# SCH_Tiny_printer_small_2024-12-16.net
KiCad netlist of a schematic drawn in EasyEDA
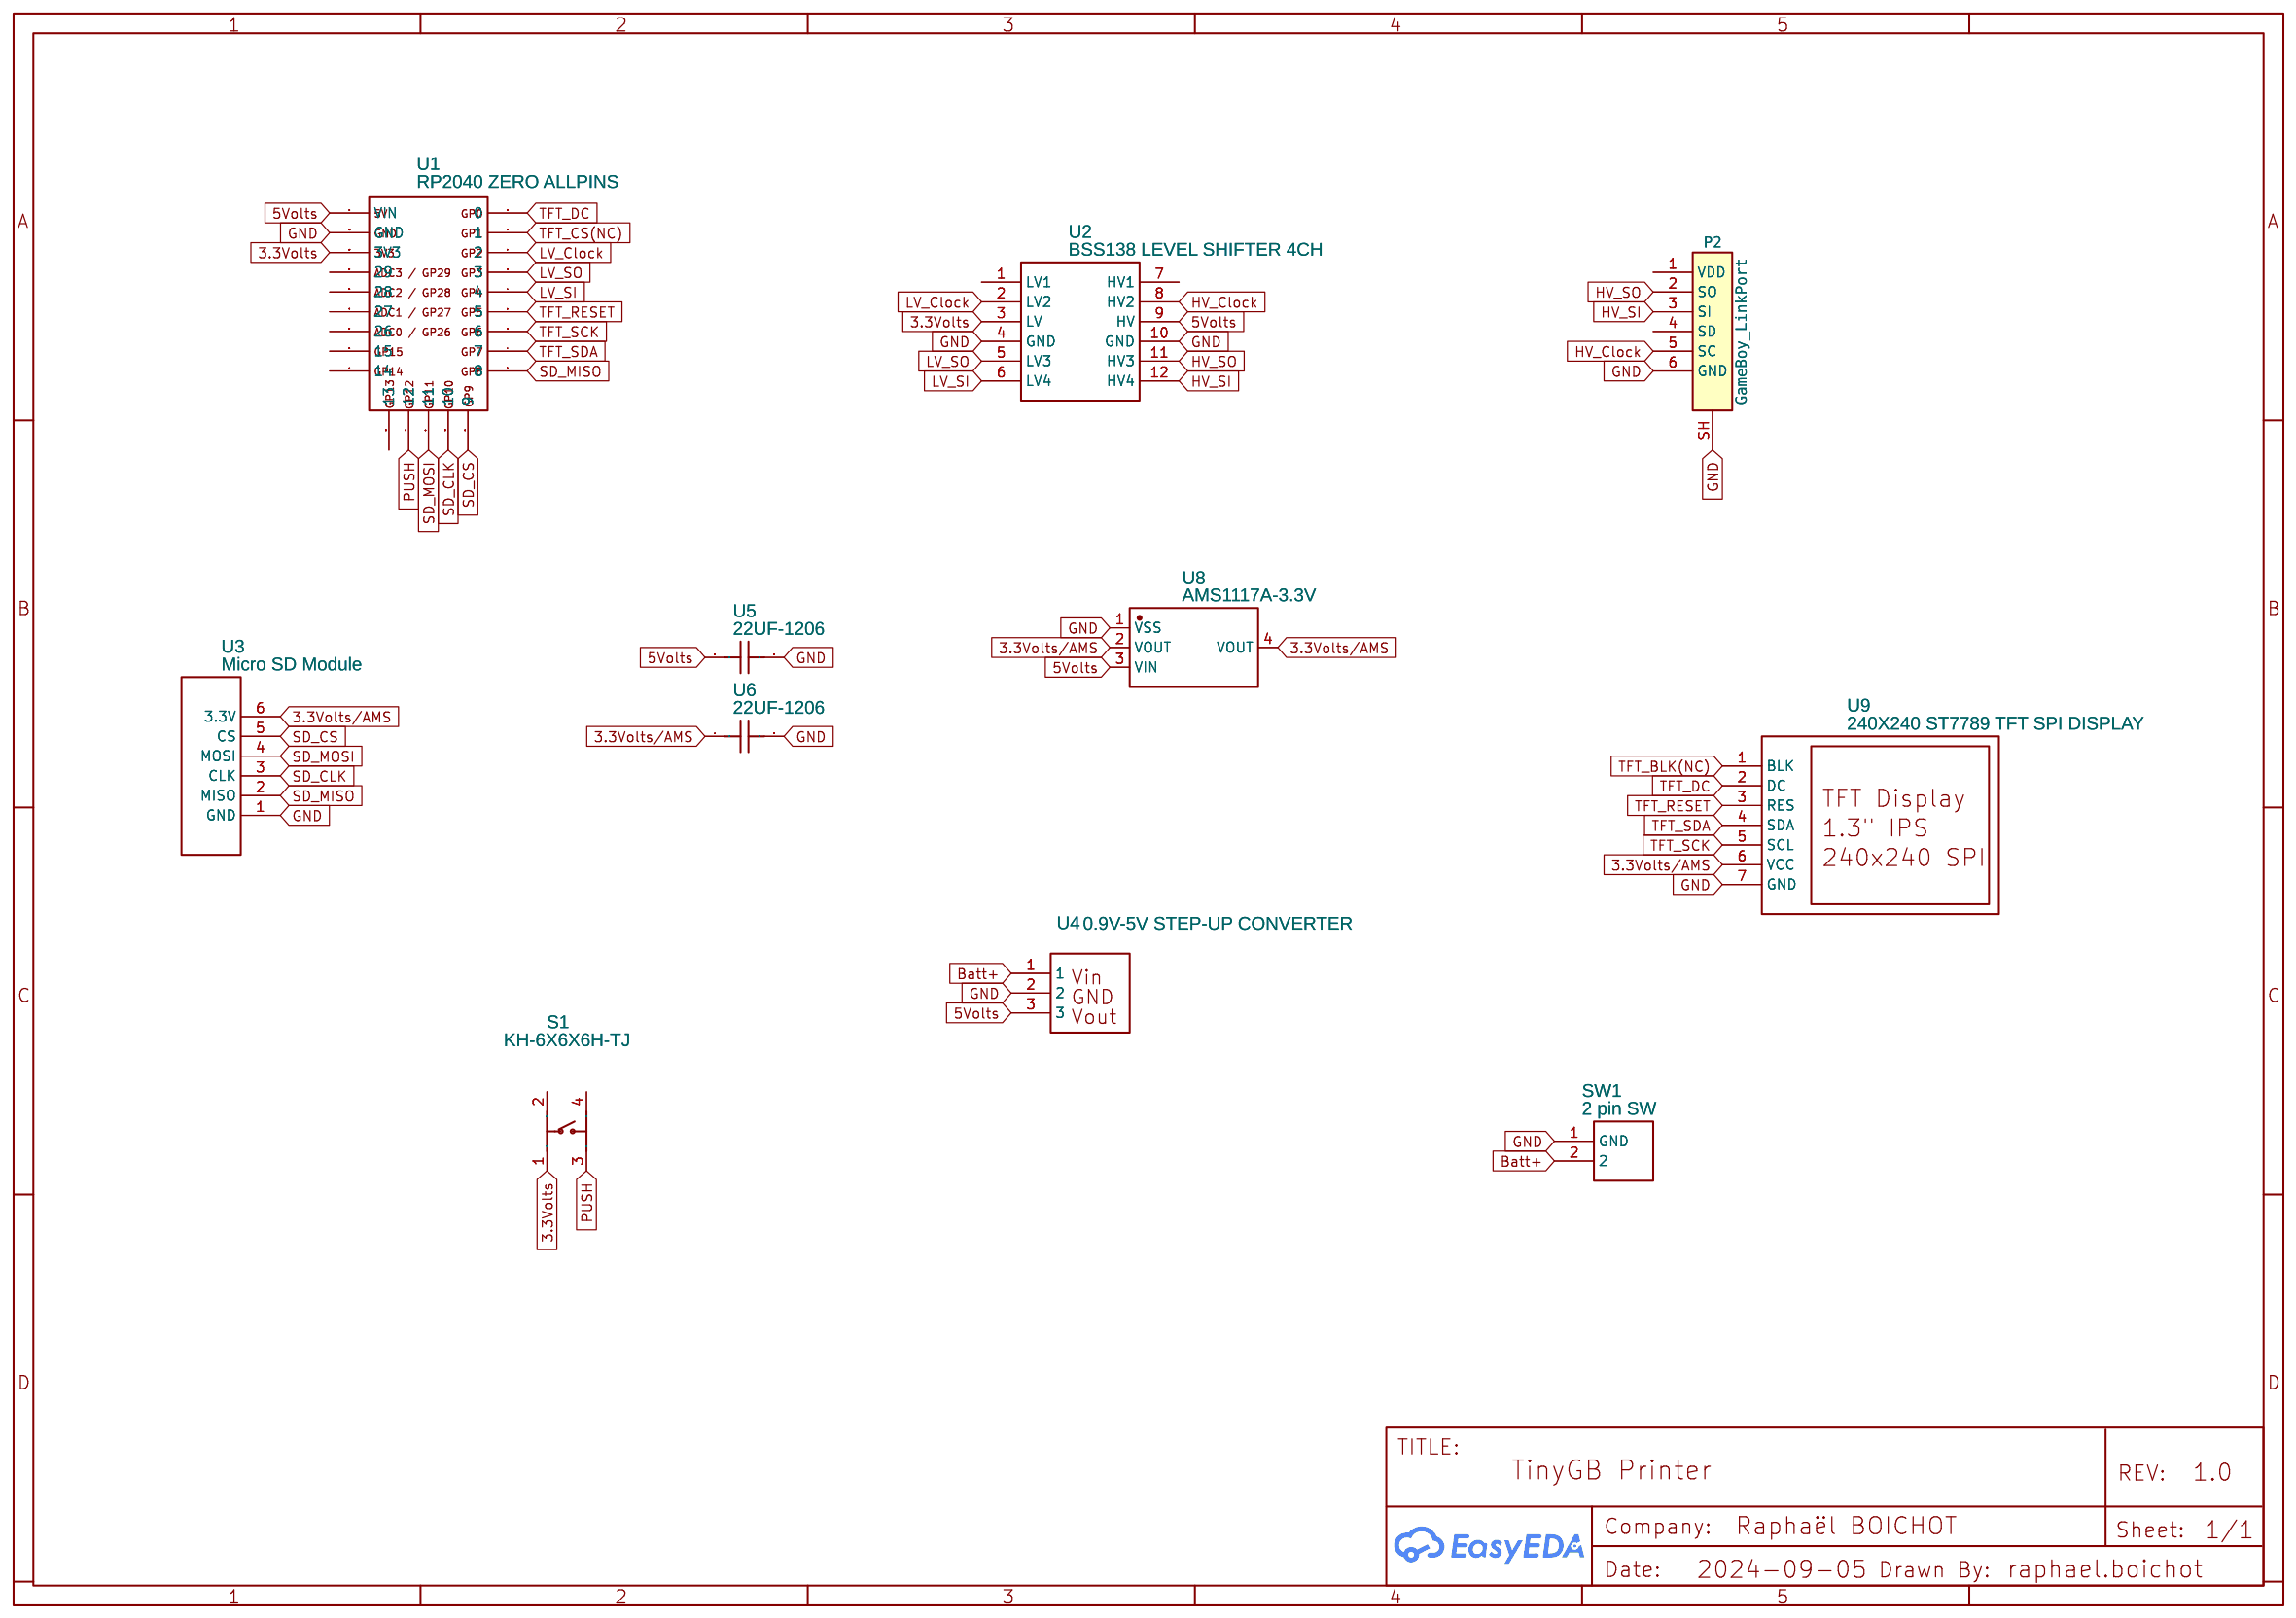
[diagram p0: schematic sheet]

(export (version "E")
  (design (tool "Eeschema 10.0.6"))
  (components
    (comp (ref "P2") (value "GameBoy_LinkPort") (libsource (lib "") (part "Unknown_860_-645")))
    (comp (ref "S1")
      (value "KH-6X6X6H-TJ")
      (fields (field (name "Manufacturer") "kinghelm(金航标)"))
      (libsource (lib "") (part "KH-6X6X6H-TJ"))
    )
    (comp (ref "SW1")
      (value "2 pin SW")
      (fields (field (name "Manufacturer") "NA"))
      (libsource (lib "") (part "2 pin SW"))
    )
    (comp (ref "U1")
      (value "RP2040 ZERO ALLPINS")
      (fields (field (name "Manufacturer Part") "RP2040 Zero") (field (name "Manufacturer") "Waveshare"))
      (libsource (lib "") (part "RP2040 ZERO ALLPINS"))
    )
    (comp (ref "U2")
      (value "BSS138 LEVEL SHIFTER 4CH")
      (fields (field (name "Manufacturer Part") "BSS138") (field (name "Manufacturer") "ON Semiconductor"))
      (libsource (lib "") (part "BSS138 LEVEL SHIFTER 4CH"))
    )
    (comp (ref "U3") (value "Micro SD Module") (libsource (lib "") (part "Micro SD Module")))
    (comp (ref "U4")
      (value "0.9V-5V STEP-UP CONVERTER")
      (fields (field (name "Manufacturer") "Generic"))
      (libsource (lib "") (part "0.9V-5V STEP-UP CONVERTER"))
    )
    (comp (ref "U5")
      (value "22UF-1206")
      (fields (field (name "Manufacturer Part") "220UF-1206"))
      (libsource (lib "") (part "220UF-1206"))
    )
    (comp (ref "U6")
      (value "22UF-1206")
      (fields (field (name "Manufacturer Part") "220UF-1206"))
      (libsource (lib "") (part "220UF-1206"))
    )
    (comp (ref "U8")
      (value "AMS1117A-3.3V")
      (fields (field (name "Manufacturer") "HX(恒佳兴)"))
      (libsource (lib "") (part "AMS1117A-3.3V"))
    )
    (comp (ref "U9")
      (value "240X240 ST7789 TFT SPI DISPLAY")
      (libsource (lib "") (part "240X240 ST7789 TFT SPI DISPLAY"))
    )
  )
  (nets
    (net (code "1") (name "3.3Volts") (class "Default")
      (node (ref "S1") (pin "1") (pinfunction "1_1") (pintype "unspecified"))
      (node (ref "U1") (pin "3V3") (pinfunction "3V3_3V3") (pintype "unspecified"))
      (node (ref "U2") (pin "3") (pinfunction "LV_3") (pintype "passive"))
    )
    (net (code "2") (name "3.3Volts{slash}AMS") (class "Default")
      (node (ref "U3") (pin "6") (pinfunction "3.3V_6") (pintype "unspecified"))
      (node (ref "U6") (pin "1") (pinfunction "1_1") (pintype "unspecified"))
      (node (ref "U8") (pin "2") (pinfunction "VOUT_2") (pintype "unspecified"))
      (node (ref "U8") (pin "4") (pinfunction "VOUT_4") (pintype "unspecified"))
      (node (ref "U9") (pin "6") (pinfunction "VCC_6") (pintype "unspecified"))
    )
    (net (code "3") (name "5Volts") (class "Default")
      (node (ref "U1") (pin "VIN") (pinfunction "VIN_VIN") (pintype "unspecified"))
      (node (ref "U2") (pin "9") (pinfunction "HV_9") (pintype "passive"))
      (node (ref "U4") (pin "3") (pinfunction "3_3") (pintype "unspecified"))
      (node (ref "U5") (pin "1") (pinfunction "1_1") (pintype "unspecified"))
      (node (ref "U8") (pin "3") (pinfunction "VIN_3") (pintype "unspecified"))
    )
    (net (code "4") (name "Batt+") (class "Default")
      (node (ref "SW1") (pin "2") (pinfunction "2_2") (pintype "unspecified"))
      (node (ref "U4") (pin "1") (pinfunction "1_1") (pintype "unspecified"))
    )
    (net (code "5") (name "GND") (class "Default")
      (node (ref "P2") (pin "6") (pinfunction "GND_6") (pintype "unspecified"))
      (node (ref "P2") (pin "SH") (pintype "unspecified"))
      (node (ref "SW1") (pin "1") (pinfunction "GND_1") (pintype "unspecified"))
      (node (ref "U1") (pin "GND") (pinfunction "GND_GND") (pintype "unspecified"))
      (node (ref "U2") (pin "10") (pinfunction "GND_10") (pintype "passive"))
      (node (ref "U2") (pin "4") (pinfunction "GND_4") (pintype "passive"))
      (node (ref "U3") (pin "1") (pinfunction "GND_1") (pintype "unspecified"))
      (node (ref "U4") (pin "2") (pinfunction "2_2") (pintype "unspecified"))
      (node (ref "U5") (pin "2") (pinfunction "2_2") (pintype "unspecified"))
      (node (ref "U6") (pin "2") (pinfunction "2_2") (pintype "unspecified"))
      (node (ref "U8") (pin "1") (pinfunction "VSS_1") (pintype "unspecified"))
      (node (ref "U9") (pin "7") (pinfunction "GND_7") (pintype "unspecified"))
    )
    (net (code "6") (name "HV_Clock") (class "Default")
      (node (ref "P2") (pin "5") (pinfunction "SC_5") (pintype "unspecified"))
      (node (ref "U2") (pin "8") (pinfunction "HV2_8") (pintype "output"))
    )
    (net (code "7") (name "HV_SI") (class "Default")
      (node (ref "P2") (pin "3") (pinfunction "SI_3") (pintype "unspecified"))
      (node (ref "U2") (pin "12") (pinfunction "HV4_12") (pintype "output"))
    )
    (net (code "8") (name "HV_SO") (class "Default")
      (node (ref "P2") (pin "2") (pinfunction "SO_2") (pintype "unspecified"))
      (node (ref "U2") (pin "11") (pinfunction "HV3_11") (pintype "output"))
    )
    (net (code "9") (name "LV_Clock") (class "Default")
      (node (ref "U1") (pin "2") (pinfunction "2_2") (pintype "unspecified"))
      (node (ref "U2") (pin "2") (pinfunction "LV2_2") (pintype "input"))
    )
    (net (code "10") (name "LV_SI") (class "Default")
      (node (ref "U1") (pin "4") (pinfunction "4_4") (pintype "unspecified"))
      (node (ref "U2") (pin "6") (pinfunction "LV4_6") (pintype "input"))
    )
    (net (code "11") (name "LV_SO") (class "Default")
      (node (ref "U1") (pin "3") (pinfunction "3_3") (pintype "unspecified"))
      (node (ref "U2") (pin "5") (pinfunction "LV3_5") (pintype "input"))
    )
    (net (code "12") (name "PUSH") (class "Default")
      (node (ref "S1") (pin "3") (pinfunction "3_3") (pintype "unspecified"))
      (node (ref "U1") (pin "12") (pinfunction "12_12") (pintype "unspecified"))
    )
    (net (code "13") (name "SD_CLK") (class "Default")
      (node (ref "U1") (pin "10") (pinfunction "10_10") (pintype "unspecified"))
      (node (ref "U3") (pin "3") (pinfunction "CLK_3") (pintype "unspecified"))
    )
    (net (code "14") (name "SD_CS") (class "Default")
      (node (ref "U1") (pin "9") (pinfunction "9_9") (pintype "unspecified"))
      (node (ref "U3") (pin "5") (pinfunction "CS_5") (pintype "unspecified"))
    )
    (net (code "15") (name "SD_MISO") (class "Default")
      (node (ref "U1") (pin "8") (pinfunction "8_8") (pintype "unspecified"))
      (node (ref "U3") (pin "2") (pinfunction "MISO_2") (pintype "unspecified"))
    )
    (net (code "16") (name "SD_MOSI") (class "Default")
      (node (ref "U1") (pin "11") (pinfunction "11_11") (pintype "unspecified"))
      (node (ref "U3") (pin "4") (pinfunction "MOSI_4") (pintype "unspecified"))
    )
    (net (code "17") (name "TFT_BLK(NC)") (class "Default")
      (node (ref "U9") (pin "1") (pinfunction "BLK_1") (pintype "unspecified"))
    )
    (net (code "18") (name "TFT_CS(NC)") (class "Default")
      (node (ref "U1") (pin "1") (pinfunction "1_1") (pintype "unspecified"))
    )
    (net (code "19") (name "TFT_DC") (class "Default")
      (node (ref "U1") (pin "0") (pinfunction "0_0") (pintype "unspecified"))
      (node (ref "U9") (pin "2") (pinfunction "DC_2") (pintype "unspecified"))
    )
    (net (code "20") (name "TFT_RESET") (class "Default")
      (node (ref "U1") (pin "5") (pinfunction "5_5") (pintype "unspecified"))
      (node (ref "U9") (pin "3") (pinfunction "RES_3") (pintype "unspecified"))
    )
    (net (code "21") (name "TFT_SCK") (class "Default")
      (node (ref "U1") (pin "6") (pinfunction "6_6") (pintype "unspecified"))
      (node (ref "U9") (pin "5") (pinfunction "SCL_5") (pintype "unspecified"))
    )
    (net (code "22") (name "TFT_SDA") (class "Default")
      (node (ref "U1") (pin "7") (pinfunction "7_7") (pintype "unspecified"))
      (node (ref "U9") (pin "4") (pinfunction "SDA_4") (pintype "unspecified"))
    )
    (net (code "23") (name "unconnected-(P2-SD-Pad4)") (class "Default")
      (node (ref "P2") (pin "4") (pinfunction "SD_4") (pintype "unspecified"))
    )
    (net (code "24") (name "unconnected-(P2-VDD-Pad1)") (class "Default")
      (node (ref "P2") (pin "1") (pinfunction "VDD_1") (pintype "unspecified"))
    )
    (net (code "25") (name "unconnected-(S1-Pad2)") (class "Default")
      (node (ref "S1") (pin "2") (pinfunction "2_2") (pintype "unspecified"))
    )
    (net (code "26") (name "unconnected-(S1-Pad4)") (class "Default")
      (node (ref "S1") (pin "4") (pinfunction "4_4") (pintype "unspecified"))
    )
    (net (code "27") (name "unconnected-(U1-Pad13)") (class "Default")
      (node (ref "U1") (pin "13") (pinfunction "13_13") (pintype "unspecified"))
    )
    (net (code "28") (name "unconnected-(U1-Pad14)") (class "Default")
      (node (ref "U1") (pin "14") (pinfunction "14_14") (pintype "unspecified"))
    )
    (net (code "29") (name "unconnected-(U1-Pad15)") (class "Default")
      (node (ref "U1") (pin "15") (pinfunction "15_15") (pintype "unspecified"))
    )
    (net (code "30") (name "unconnected-(U1-Pad26)") (class "Default")
      (node (ref "U1") (pin "26") (pinfunction "26_26") (pintype "unspecified"))
    )
    (net (code "31") (name "unconnected-(U1-Pad27)") (class "Default")
      (node (ref "U1") (pin "27") (pinfunction "27_27") (pintype "unspecified"))
    )
    (net (code "32") (name "unconnected-(U1-Pad28)") (class "Default")
      (node (ref "U1") (pin "28") (pinfunction "28_28") (pintype "unspecified"))
    )
    (net (code "33") (name "unconnected-(U1-Pad29)") (class "Default")
      (node (ref "U1") (pin "29") (pinfunction "29_29") (pintype "unspecified"))
    )
    (net (code "34") (name "unconnected-(U2-HV1-Pad7)") (class "Default")
      (node (ref "U2") (pin "7") (pinfunction "HV1_7") (pintype "output"))
    )
    (net (code "35") (name "unconnected-(U2-LV1-Pad1)") (class "Default")
      (node (ref "U2") (pin "1") (pinfunction "LV1_1") (pintype "input"))
    )
  )
)
